# V2.net
KiCad netlist of a schematic drawn in Altium Designer
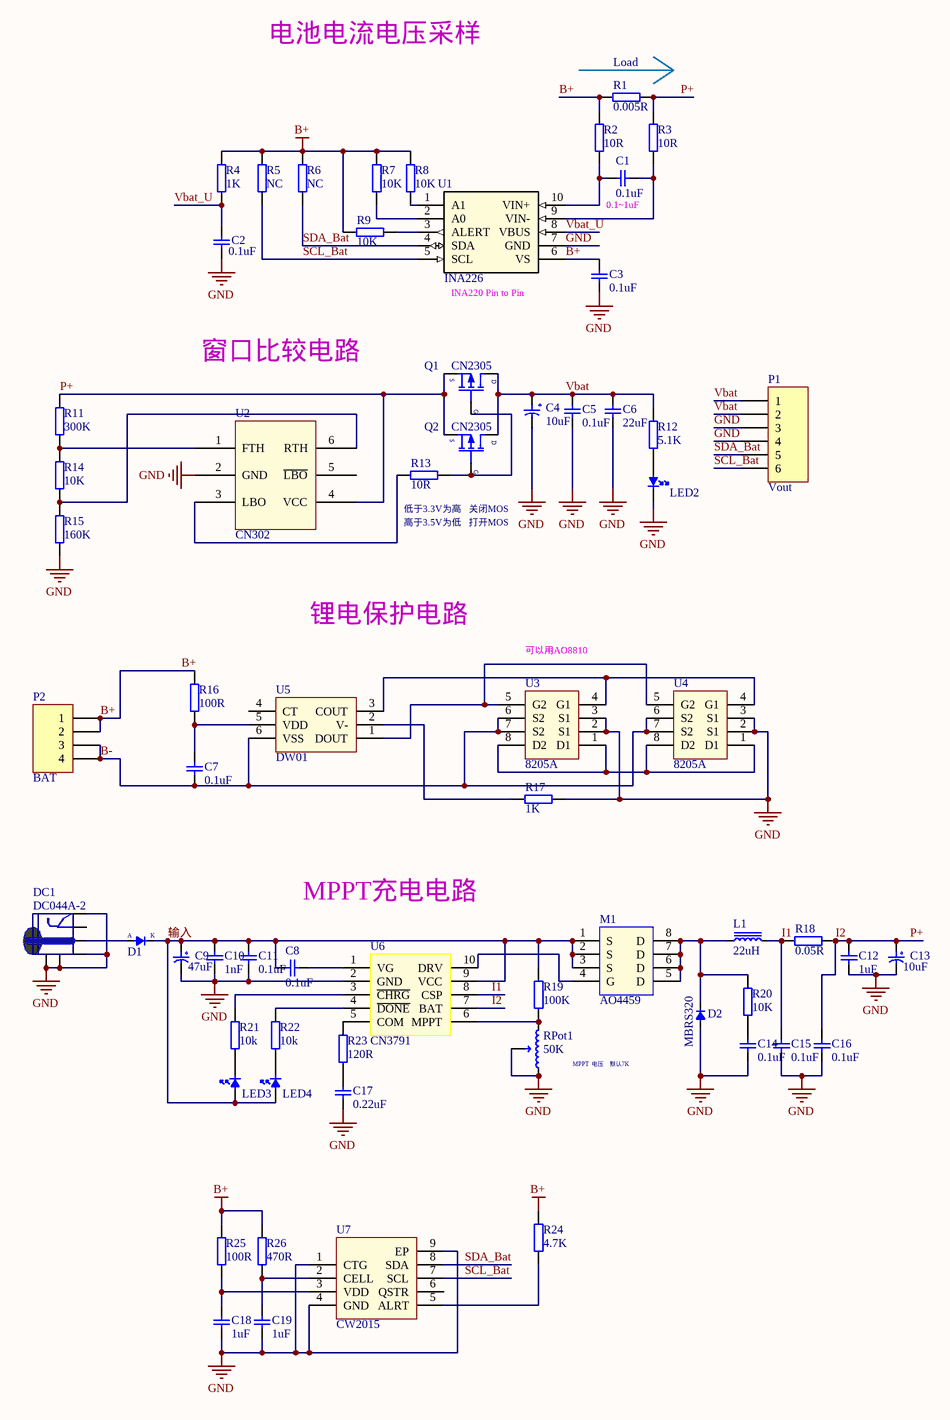
[diagram p0: 充放电模块V2.SchDoc]

(export (version "E")
  (design (tool "Eeschema 10.0.6"))
  (components
    (comp (ref "C1")
      (value "0.1uF")
      (footprint "0603-C")
      (description "Capacitor")
      (fields (field (name "PUBLISHER") "Altium Limited"))
      (libsource (lib "Schlib") (part "Cap"))
    )
    (comp (ref "C2")
      (value "0.1uF")
      (footprint "0603-C")
      (description "Capacitor")
      (fields (field (name "PUBLISHER") "Altium Limited"))
      (libsource (lib "Schlib") (part "Cap"))
    )
    (comp (ref "C3")
      (value "0.1uF")
      (footprint "0603-C")
      (description "Capacitor")
      (fields (field (name "PUBLISHER") "Altium Limited"))
      (libsource (lib "Schlib") (part "Cap"))
    )
    (comp (ref "C4") (value "10uF") (footprint "C6.3X6.3") (libsource (lib "") (part "Cap 有极性_1")))
    (comp (ref "C5")
      (value "0.1uF")
      (footprint "0603-C")
      (description "Capacitor")
      (fields (field (name "PUBLISHER") "Altium Limited"))
      (libsource (lib "Schlib") (part "Cap"))
    )
    (comp (ref "C6")
      (value "22uF")
      (footprint "1206 C")
      (description "Capacitor")
      (fields (field (name "PUBLISHER") "Altium Limited"))
      (libsource (lib "Schlib") (part "Cap"))
    )
    (comp (ref "C7")
      (value "0.1uF")
      (footprint "0603-C")
      (description "Capacitor")
      (fields (field (name "PUBLISHER") "Altium Limited"))
      (libsource (lib "Schlib") (part "Cap"))
    )
    (comp (ref "C8")
      (value "0.1uF")
      (footprint "0603-C")
      (description "Capacitor")
      (fields (field (name "PUBLISHER") "Altium Limited"))
      (libsource (lib "Schlib") (part "Cap"))
    )
    (comp (ref "C9") (value "47uF") (footprint "C8X8") (libsource (lib "Schlib") (part "Cap 有极性")))
    (comp (ref "C10")
      (value "1nF")
      (footprint "0603-C")
      (description "Capacitor")
      (fields (field (name "PUBLISHER") "Altium Limited"))
      (libsource (lib "Schlib") (part "Cap"))
    )
    (comp (ref "C11")
      (value "0.1uF")
      (footprint "0603-C")
      (description "Capacitor")
      (fields (field (name "PUBLISHER") "Altium Limited"))
      (libsource (lib "Schlib") (part "Cap"))
    )
    (comp (ref "C12")
      (value "1uF")
      (footprint "0603-C")
      (description "Capacitor")
      (fields (field (name "PUBLISHER") "Altium Limited"))
      (libsource (lib "Schlib") (part "Cap"))
    )
    (comp (ref "C13") (value "10uF") (footprint "C6.3X6.3") (libsource (lib "Schlib") (part "Cap 有极性")))
    (comp (ref "C14")
      (value "0.1uF")
      (footprint "0603-C")
      (description "Capacitor")
      (fields (field (name "PUBLISHER") "Altium Limited"))
      (libsource (lib "Schlib") (part "Cap"))
    )
    (comp (ref "C15")
      (value "0.1uF")
      (footprint "0603-C")
      (description "Capacitor")
      (fields (field (name "PUBLISHER") "Altium Limited"))
      (libsource (lib "Schlib") (part "Cap"))
    )
    (comp (ref "C16")
      (value "0.1uF")
      (footprint "0603-C")
      (description "Capacitor")
      (fields (field (name "PUBLISHER") "Altium Limited"))
      (libsource (lib "Schlib") (part "Cap"))
    )
    (comp (ref "C17")
      (value "0.22uF")
      (footprint "0603-C")
      (description "Capacitor")
      (fields (field (name "PUBLISHER") "Altium Limited"))
      (libsource (lib "Schlib") (part "Cap"))
    )
    (comp (ref "C18")
      (value "1uF")
      (footprint "0603-C")
      (description "Capacitor")
      (fields (field (name "PUBLISHER") "Altium Limited"))
      (libsource (lib "Schlib") (part "Cap"))
    )
    (comp (ref "C19")
      (value "1uF")
      (footprint "0603-C")
      (description "Capacitor")
      (fields (field (name "PUBLISHER") "Altium Limited"))
      (libsource (lib "Schlib") (part "Cap"))
    )
    (comp (ref "D1") (value "二极管") (footprint "DO-214") (libsource (lib "Schlib") (part "D")))
    (comp (ref "D2") (value "MBRS320") (footprint "DO-214AB") (libsource (lib "Schlib") (part "1N4148")))
    (comp (ref "DC1")
      (value "DC044A-2")
      (footprint "DC044A 6PIN")
      (description "6PIN")
      (libsource (lib "Schlib") (part "DC044A-2"))
    )
    (comp (ref "L1")
      (value "22uH")
      (footprint "L7X7")
      (description "Inductor")
      (fields (field (name "PUBLISHER") "Altium Limited"))
      (libsource (lib "Schlib") (part "Inductor"))
    )
    (comp (ref "LED2") (value "LED") (footprint "LED0805G") (libsource (lib "Schlib") (part "LED")))
    (comp (ref "LED3") (value "LED") (footprint "LED0805R") (libsource (lib "Schlib") (part "LED")))
    (comp (ref "LED4") (value "LED") (footprint "LED0805G") (libsource (lib "Schlib") (part "LED")))
    (comp (ref "M1") (value "AO4459") (footprint "SOP8") (libsource (lib "Schlib") (part "AO4459")))
    (comp (ref "P1")
      (value "Vout")
      (footprint "XHS2.5-6P")
      (description "Header, 6-Pin")
      (fields (field (name "PUBLISHER") "Altium Limited"))
      (libsource (lib "Miscellaneous Connectors") (part "Header 6"))
    )
    (comp (ref "P2")
      (value "BAT")
      (footprint "XH 2.5 AW 4PIN")
      (description "Header, 4-Pin")
      (fields (field (name "PUBLISHER") "Altium Limited"))
      (libsource (lib "Miscellaneous Connectors") (part "Header 4"))
    )
    (comp (ref "Q1") (value "CN2305") (footprint "SOT23") (libsource (lib "Schlib") (part "CN2305")))
    (comp (ref "Q2") (value "CN2305") (footprint "SOT23") (libsource (lib "Schlib") (part "CN2305")))
    (comp (ref "R1")
      (value "0.005R")
      (footprint "1210R")
      (description "Resistor")
      (libsource (lib "") (part "Res2_3"))
    )
    (comp (ref "R2")
      (value "10R")
      (footprint "0603-r")
      (description "Resistor")
      (libsource (lib "Schlib") (part "Res2"))
    )
    (comp (ref "R3")
      (value "10R")
      (footprint "0603-r")
      (description "Resistor")
      (libsource (lib "Schlib") (part "Res2"))
    )
    (comp (ref "R4")
      (value "1K")
      (footprint "0603-r")
      (description "Resistor")
      (libsource (lib "") (part "Res2_1"))
    )
    (comp (ref "R5")
      (value "NC")
      (footprint "0603-r")
      (description "Resistor")
      (libsource (lib "Schlib") (part "Res2"))
    )
    (comp (ref "R6")
      (value "NC")
      (footprint "0603-r")
      (description "Resistor")
      (libsource (lib "Schlib") (part "Res2"))
    )
    (comp (ref "R7")
      (value "10K")
      (footprint "0603-r")
      (description "Resistor")
      (libsource (lib "Schlib") (part "Res2"))
    )
    (comp (ref "R8")
      (value "10K")
      (footprint "0603-r")
      (description "Resistor")
      (libsource (lib "Schlib") (part "Res2"))
    )
    (comp (ref "R9")
      (value "10K")
      (footprint "0603-r")
      (description "Resistor")
      (libsource (lib "") (part "Res2_1"))
    )
    (comp (ref "R11")
      (value "300K")
      (footprint "0603-r")
      (description "Resistor")
      (libsource (lib "") (part "Res2_3"))
    )
    (comp (ref "R12")
      (value "5.1K")
      (footprint "0603-r")
      (description "Resistor")
      (libsource (lib "") (part "Res2_2"))
    )
    (comp (ref "R13")
      (value "10R")
      (footprint "0603-r")
      (description "Resistor")
      (libsource (lib "") (part "Res2_2"))
    )
    (comp (ref "R14")
      (value "10K")
      (footprint "0603-r")
      (description "Resistor")
      (libsource (lib "") (part "Res2_3"))
    )
    (comp (ref "R15")
      (value "160K")
      (footprint "0603-r")
      (description "Resistor")
      (libsource (lib "") (part "Res2_3"))
    )
    (comp (ref "R16")
      (value "100R")
      (footprint "0603-r")
      (description "Resistor")
      (libsource (lib "") (part "Res2_1"))
    )
    (comp (ref "R17")
      (value "1K")
      (footprint "0603-r")
      (description "Resistor")
      (libsource (lib "") (part "Res2_3"))
    )
    (comp (ref "R18")
      (value "0.05R")
      (footprint "1210R")
      (description "Resistor")
      (libsource (lib "") (part "Res2_3"))
    )
    (comp (ref "R19")
      (value "100K")
      (footprint "0603-r")
      (description "Resistor")
      (libsource (lib "") (part "Res2_2"))
    )
    (comp (ref "R20")
      (value "10K")
      (footprint "0603-r")
      (description "Resistor")
      (libsource (lib "") (part "Res2_2"))
    )
    (comp (ref "R21")
      (value "10k")
      (footprint "0603-r")
      (description "Resistor")
      (libsource (lib "") (part "Res2_2"))
    )
    (comp (ref "R22")
      (value "10k")
      (footprint "0603-r")
      (description "Resistor")
      (libsource (lib "") (part "Res2_2"))
    )
    (comp (ref "R23")
      (value "120R")
      (footprint "0603-r")
      (description "Resistor")
      (libsource (lib "") (part "Res2_2"))
    )
    (comp (ref "R24")
      (value "4.7K")
      (footprint "0603-r")
      (description "Resistor")
      (libsource (lib "") (part "Res2_2"))
    )
    (comp (ref "R25")
      (value "100R")
      (footprint "0603-r")
      (description "Resistor")
      (libsource (lib "") (part "Res2_2"))
    )
    (comp (ref "R26")
      (value "470R")
      (footprint "0603-r")
      (description "Resistor")
      (libsource (lib "") (part "Res2_2"))
    )
    (comp (ref "RPot1") (value "50K") (footprint "VR5 - W") (libsource (lib "Schlib") (part "可调电阻")))
    (comp (ref "U1")
      (value "INA226")
      (footprint "DGS10")
      (description "Imported")
      (fields
        (field (name "MANUFACTURER") "Texas Instruments")
        (field (name "MANUFACTURER_PART_NUMBER") "ina226_dgs_10")
      )
      (libsource (lib "Schlib") (part "INA226_DGS_10"))
    )
    (comp (ref "U2")
      (value "CN302")
      (footprint "其他:SOT23-6")
      (description "如韵电池检测")
      (libsource (lib "Schlib") (part "CN302"))
    )
    (comp (ref "U3") (value "8205A") (footprint "TSSOP8-MCP730P") (libsource (lib "Schlib") (part "8205A")))
    (comp (ref "U4") (value "8205A") (footprint "TSSOP8-MCP730P") (libsource (lib "Schlib") (part "8205A")))
    (comp (ref "U5") (value "DW01") (footprint "SOT23-6") (libsource (lib "Schlib") (part "DW01")))
    (comp (ref "U6") (value "CN3791") (footprint "SSOP10") (libsource (lib "Schlib") (part "CN3791")))
    (comp (ref "U7") (value "CW2015") (footprint "QFN-8") (libsource (lib "Schlib") (part "CW2015")))
  )
  (nets
    (net (code "1") (name "/B-") (class "Default")
      (node (ref "C7") (pin "2") (pinfunction "2_2") (pintype "passive"))
      (node (ref "P2") (pin "3") (pinfunction "3_3") (pintype "passive"))
      (node (ref "P2") (pin "4") (pinfunction "4_4") (pintype "passive"))
      (node (ref "U3") (pin "6") (pinfunction "S2_6") (pintype "passive"))
      (node (ref "U3") (pin "7") (pinfunction "S2_7") (pintype "passive"))
      (node (ref "U4") (pin "6") (pinfunction "S2_6") (pintype "passive"))
      (node (ref "U4") (pin "7") (pinfunction "S2_7") (pintype "passive"))
      (node (ref "U5") (pin "6") (pinfunction "VSS_6") (pintype "passive"))
    )
    (net (code "2") (name "/I1") (class "Default")
      (node (ref "C15") (pin "1") (pinfunction "1_1") (pintype "passive"))
      (node (ref "L1") (pin "2") (pinfunction "2_2") (pintype "passive"))
      (node (ref "R18") (pin "2") (pinfunction "2_2") (pintype "passive"))
      (node (ref "U6") (pin "8") (pinfunction "CSP_8") (pintype "passive"))
    )
    (net (code "3") (name "/I2") (class "Default")
      (node (ref "C12") (pin "1") (pinfunction "1_1") (pintype "passive"))
      (node (ref "C13") (pin "1") (pinfunction "1_1") (pintype "passive"))
      (node (ref "C16") (pin "1") (pinfunction "1_1") (pintype "passive"))
      (node (ref "Q1") (pin "3") (pinfunction "S_3") (pintype "passive"))
      (node (ref "Q2") (pin "3") (pinfunction "S_3") (pintype "passive"))
      (node (ref "R1") (pin "1") (pinfunction "1_1") (pintype "passive"))
      (node (ref "R11") (pin "1") (pinfunction "1_1") (pintype "passive"))
      (node (ref "R18") (pin "1") (pinfunction "1_1") (pintype "passive"))
      (node (ref "R3") (pin "2") (pinfunction "2_2") (pintype "passive"))
      (node (ref "U2") (pin "4") (pinfunction "VCC_4") (pintype "passive"))
      (node (ref "U6") (pin "7") (pinfunction "BAT_7") (pintype "passive"))
    )
    (net (code "4") (name "/SCL_Bat") (class "Default")
      (node (ref "P1") (pin "6") (pinfunction "6_6") (pintype "passive"))
      (node (ref "R5") (pin "1") (pinfunction "1_1") (pintype "passive"))
      (node (ref "U1") (pin "5") (pinfunction "SCL_5") (pintype "input"))
      (node (ref "U7") (pin "7") (pinfunction "SCL_7") (pintype "passive"))
    )
    (net (code "5") (name "/SDA_Bat") (class "Default")
      (node (ref "P1") (pin "5") (pinfunction "5_5") (pintype "passive"))
      (node (ref "R6") (pin "1") (pinfunction "1_1") (pintype "passive"))
      (node (ref "U1") (pin "4") (pinfunction "SDA_4") (pintype "bidirectional"))
      (node (ref "U7") (pin "8") (pinfunction "SDA_8") (pintype "passive"))
    )
    (net (code "6") (name "/Vbat") (class "Default")
      (node (ref "C4") (pin "1") (pinfunction "1_1") (pintype "passive"))
      (node (ref "C5") (pin "1") (pinfunction "1_1") (pintype "passive"))
      (node (ref "C6") (pin "1") (pinfunction "1_1") (pintype "passive"))
      (node (ref "P1") (pin "1") (pinfunction "1_1") (pintype "passive"))
      (node (ref "P1") (pin "2") (pinfunction "2_2") (pintype "passive"))
      (node (ref "Q1") (pin "2") (pinfunction "D_2") (pintype "passive"))
      (node (ref "Q2") (pin "2") (pinfunction "D_2") (pintype "passive"))
      (node (ref "R12") (pin "2") (pinfunction "2_2") (pintype "passive"))
    )
    (net (code "7") (name "/Vbat_U") (class "Default")
      (node (ref "C2") (pin "2") (pinfunction "2_2") (pintype "passive"))
      (node (ref "R4") (pin "2") (pinfunction "2_2") (pintype "passive"))
      (node (ref "U1") (pin "8") (pinfunction "VBUS_8") (pintype "input"))
    )
    (net (code "8") (name "/输入") (class "Default")
      (node (ref "C10") (pin "1") (pinfunction "1_1") (pintype "passive"))
      (node (ref "C11") (pin "1") (pinfunction "1_1") (pintype "passive"))
      (node (ref "C8") (pin "2") (pinfunction "2_2") (pintype "passive"))
      (node (ref "C9") (pin "1") (pinfunction "1_1") (pintype "passive"))
      (node (ref "D1") (pin "2") (pinfunction "K_2") (pintype "passive"))
      (node (ref "LED3") (pin "1") (pinfunction "1_1") (pintype "passive"))
      (node (ref "LED4") (pin "1") (pinfunction "1_1") (pintype "passive"))
      (node (ref "M1") (pin "1") (pinfunction "S_1") (pintype "passive"))
      (node (ref "M1") (pin "2") (pinfunction "S_2") (pintype "passive"))
      (node (ref "M1") (pin "3") (pinfunction "S_3") (pintype "passive"))
      (node (ref "R19") (pin "2") (pinfunction "2_2") (pintype "passive"))
      (node (ref "U6") (pin "9") (pinfunction "VCC_9") (pintype "passive"))
    )
    (net (code "9") (name "B+") (class "Default")
      (node (ref "C3") (pin "1") (pinfunction "1_1") (pintype "passive"))
      (node (ref "P2") (pin "1") (pinfunction "1_1") (pintype "passive"))
      (node (ref "P2") (pin "2") (pinfunction "2_2") (pintype "passive"))
      (node (ref "R1") (pin "2") (pinfunction "2_2") (pintype "passive"))
      (node (ref "R16") (pin "1") (pinfunction "1_1") (pintype "passive"))
      (node (ref "R2") (pin "2") (pinfunction "2_2") (pintype "passive"))
      (node (ref "R24") (pin "2") (pinfunction "2_2") (pintype "passive"))
      (node (ref "R25") (pin "2") (pinfunction "2_2") (pintype "passive"))
      (node (ref "R26") (pin "2") (pinfunction "2_2") (pintype "passive"))
      (node (ref "R4") (pin "1") (pinfunction "1_1") (pintype "passive"))
      (node (ref "R5") (pin "2") (pinfunction "2_2") (pintype "passive"))
      (node (ref "R6") (pin "2") (pinfunction "2_2") (pintype "passive"))
      (node (ref "R7") (pin "2") (pinfunction "2_2") (pintype "passive"))
      (node (ref "R8") (pin "2") (pinfunction "2_2") (pintype "passive"))
      (node (ref "R9") (pin "2") (pinfunction "2_2") (pintype "passive"))
      (node (ref "U1") (pin "6") (pinfunction "VS_6") (pintype "power_in"))
    )
    (net (code "10") (name "GND") (class "Default")
      (node (ref "C10") (pin "2") (pinfunction "2_2") (pintype "passive"))
      (node (ref "C11") (pin "2") (pinfunction "2_2") (pintype "passive"))
      (node (ref "C12") (pin "2") (pinfunction "2_2") (pintype "passive"))
      (node (ref "C13") (pin "2") (pinfunction "2_2") (pintype "passive"))
      (node (ref "C14") (pin "2") (pinfunction "2_2") (pintype "passive"))
      (node (ref "C15") (pin "2") (pinfunction "2_2") (pintype "passive"))
      (node (ref "C16") (pin "2") (pinfunction "2_2") (pintype "passive"))
      (node (ref "C17") (pin "2") (pinfunction "2_2") (pintype "passive"))
      (node (ref "C18") (pin "1") (pinfunction "1_1") (pintype "passive"))
      (node (ref "C19") (pin "1") (pinfunction "1_1") (pintype "passive"))
      (node (ref "C2") (pin "1") (pinfunction "1_1") (pintype "passive"))
      (node (ref "C3") (pin "2") (pinfunction "2_2") (pintype "passive"))
      (node (ref "C4") (pin "2") (pinfunction "2_2") (pintype "passive"))
      (node (ref "C5") (pin "2") (pinfunction "2_2") (pintype "passive"))
      (node (ref "C6") (pin "2") (pinfunction "2_2") (pintype "passive"))
      (node (ref "C9") (pin "2") (pinfunction "2_2") (pintype "passive"))
      (node (ref "D2") (pin "1") (pinfunction "1_1") (pintype "passive"))
      (node (ref "DC1") (pin "1") (pinfunction "1_1") (pintype "passive"))
      (node (ref "DC1") (pin "2") (pinfunction "2_2") (pintype "passive"))
      (node (ref "DC1") (pin "4") (pinfunction "4_4") (pintype "passive"))
      (node (ref "DC1") (pin "5") (pinfunction "5_5") (pintype "passive"))
      (node (ref "LED2") (pin "2") (pinfunction "2_2") (pintype "passive"))
      (node (ref "P1") (pin "3") (pinfunction "3_3") (pintype "passive"))
      (node (ref "P1") (pin "4") (pinfunction "4_4") (pintype "passive"))
      (node (ref "R15") (pin "2") (pinfunction "2_2") (pintype "passive"))
      (node (ref "R17") (pin "1") (pinfunction "1_1") (pintype "passive"))
      (node (ref "RPot1") (pin "1") (pinfunction "1_1") (pintype "passive"))
      (node (ref "RPot1") (pin "2") (pinfunction "2_2") (pintype "passive"))
      (node (ref "U1") (pin "7") (pinfunction "GND_7") (pintype "power_in"))
      (node (ref "U2") (pin "2") (pinfunction "GND_2") (pintype "passive"))
      (node (ref "U3") (pin "2") (pinfunction "S1_2") (pintype "passive"))
      (node (ref "U3") (pin "3") (pinfunction "S1_3") (pintype "passive"))
      (node (ref "U4") (pin "2") (pinfunction "S1_2") (pintype "passive"))
      (node (ref "U4") (pin "3") (pinfunction "S1_3") (pintype "passive"))
      (node (ref "U6") (pin "2") (pinfunction "GND_2") (pintype "passive"))
      (node (ref "U7") (pin "1") (pinfunction "CTG_1") (pintype "passive"))
      (node (ref "U7") (pin "4") (pinfunction "GND_4") (pintype "passive"))
      (node (ref "U7") (pin "9") (pinfunction "EP_9") (pintype "passive"))
    )
    (net (code "11") (name "Net-(C14-Pad1)") (class "Default")
      (node (ref "C14") (pin "1") (pinfunction "1_1") (pintype "passive"))
      (node (ref "R20") (pin "1") (pinfunction "1_1") (pintype "passive"))
    )
    (net (code "12") (name "Net-(C17-Pad1)") (class "Default")
      (node (ref "C17") (pin "1") (pinfunction "1_1") (pintype "passive"))
      (node (ref "R23") (pin "1") (pinfunction "1_1") (pintype "passive"))
    )
    (net (code "13") (name "Net-(D1-A)") (class "Default")
      (node (ref "D1") (pin "1") (pinfunction "A_1") (pintype "passive"))
      (node (ref "DC1") (pin "3") (pinfunction "3_3") (pintype "passive"))
    )
    (net (code "14") (name "Net-(D2-Pad2)") (class "Default")
      (node (ref "D2") (pin "2") (pinfunction "2_2") (pintype "passive"))
      (node (ref "L1") (pin "1") (pinfunction "1_1") (pintype "passive"))
      (node (ref "M1") (pin "5") (pinfunction "D_5") (pintype "passive"))
      (node (ref "M1") (pin "6") (pinfunction "D_6") (pintype "passive"))
      (node (ref "M1") (pin "7") (pinfunction "D_7") (pintype "passive"))
      (node (ref "M1") (pin "8") (pinfunction "D_8") (pintype "passive"))
      (node (ref "R20") (pin "2") (pinfunction "2_2") (pintype "passive"))
    )
    (net (code "15") (name "Net-(LED2-Pad1)") (class "Default")
      (node (ref "LED2") (pin "1") (pinfunction "1_1") (pintype "passive"))
      (node (ref "R12") (pin "1") (pinfunction "1_1") (pintype "passive"))
    )
    (net (code "16") (name "Net-(LED3-Pad2)") (class "Default")
      (node (ref "LED3") (pin "2") (pinfunction "2_2") (pintype "passive"))
      (node (ref "R21") (pin "1") (pinfunction "1_1") (pintype "passive"))
    )
    (net (code "17") (name "Net-(LED4-Pad2)") (class "Default")
      (node (ref "LED4") (pin "2") (pinfunction "2_2") (pintype "passive"))
      (node (ref "R22") (pin "1") (pinfunction "1_1") (pintype "passive"))
    )
    (net (code "18") (name "Net-(M1-G)") (class "Default")
      (node (ref "M1") (pin "4") (pinfunction "G_4") (pintype "passive"))
      (node (ref "U6") (pin "10") (pinfunction "DRV_10") (pintype "passive"))
    )
    (net (code "19") (name "Net-(Q1-G)") (class "Default")
      (node (ref "Q1") (pin "1") (pinfunction "G_1") (pintype "passive"))
      (node (ref "Q2") (pin "1") (pinfunction "G_1") (pintype "passive"))
      (node (ref "R13") (pin "2") (pinfunction "2_2") (pintype "passive"))
    )
    (net (code "20") (name "Net-(U1-A0)") (class "Default")
      (node (ref "R7") (pin "1") (pinfunction "1_1") (pintype "passive"))
      (node (ref "U1") (pin "2") (pinfunction "A0_2") (pintype "passive"))
    )
    (net (code "21") (name "Net-(U1-A1)") (class "Default")
      (node (ref "R8") (pin "1") (pinfunction "1_1") (pintype "passive"))
      (node (ref "U1") (pin "1") (pinfunction "A1_1") (pintype "passive"))
    )
    (net (code "22") (name "Net-(U1-ALERT)") (class "Default")
      (node (ref "R9") (pin "1") (pinfunction "1_1") (pintype "passive"))
      (node (ref "U1") (pin "3") (pinfunction "ALERT_3") (pintype "output"))
    )
    (net (code "23") (name "Net-(U1-VIN+)") (class "Default")
      (node (ref "C1") (pin "2") (pinfunction "2_2") (pintype "passive"))
      (node (ref "R2") (pin "1") (pinfunction "1_1") (pintype "passive"))
      (node (ref "U1") (pin "10") (pinfunction "VIN+_10") (pintype "input"))
    )
    (net (code "24") (name "Net-(U1-VIN-)") (class "Default")
      (node (ref "C1") (pin "1") (pinfunction "1_1") (pintype "passive"))
      (node (ref "R3") (pin "1") (pinfunction "1_1") (pintype "passive"))
      (node (ref "U1") (pin "9") (pinfunction "VIN-_9") (pintype "input"))
    )
    (net (code "25") (name "Net-(U2-FTH)") (class "Default")
      (node (ref "R11") (pin "2") (pinfunction "2_2") (pintype "passive"))
      (node (ref "R14") (pin "1") (pinfunction "1_1") (pintype "passive"))
      (node (ref "U2") (pin "1") (pinfunction "FTH_1") (pintype "passive"))
    )
    (net (code "26") (name "Net-(U2-LBO)") (class "Default")
      (node (ref "R13") (pin "1") (pinfunction "1_1") (pintype "passive"))
      (node (ref "U2") (pin "3") (pinfunction "LBO_3") (pintype "passive"))
    )
    (net (code "27") (name "Net-(U2-RTH)") (class "Default")
      (node (ref "R14") (pin "2") (pinfunction "2_2") (pintype "passive"))
      (node (ref "R15") (pin "1") (pinfunction "1_1") (pintype "passive"))
      (node (ref "U2") (pin "6") (pinfunction "RTH_6") (pintype "passive"))
    )
    (net (code "28") (name "Net-(U3-D1)") (class "Default")
      (node (ref "U3") (pin "1") (pinfunction "D1_1") (pintype "passive"))
      (node (ref "U3") (pin "8") (pinfunction "D2_8") (pintype "passive"))
      (node (ref "U4") (pin "1") (pinfunction "D1_1") (pintype "passive"))
      (node (ref "U4") (pin "8") (pinfunction "D2_8") (pintype "passive"))
    )
    (net (code "29") (name "Net-(U3-G1)") (class "Default")
      (node (ref "U3") (pin "4") (pinfunction "G1_4") (pintype "passive"))
      (node (ref "U4") (pin "4") (pinfunction "G1_4") (pintype "passive"))
      (node (ref "U5") (pin "3") (pinfunction "COUT_3") (pintype "passive"))
    )
    (net (code "30") (name "Net-(U3-G2)") (class "Default")
      (node (ref "U3") (pin "5") (pinfunction "G2_5") (pintype "passive"))
      (node (ref "U4") (pin "5") (pinfunction "G2_5") (pintype "passive"))
      (node (ref "U5") (pin "1") (pinfunction "DOUT_1") (pintype "passive"))
    )
    (net (code "31") (name "Net-(U5-V-)") (class "Default")
      (node (ref "R17") (pin "2") (pinfunction "2_2") (pintype "passive"))
      (node (ref "U5") (pin "2") (pinfunction "V-_2") (pintype "passive"))
    )
    (net (code "32") (name "Net-(U5-VDD)") (class "Default")
      (node (ref "C7") (pin "1") (pinfunction "1_1") (pintype "passive"))
      (node (ref "R16") (pin "2") (pinfunction "2_2") (pintype "passive"))
      (node (ref "U5") (pin "5") (pinfunction "VDD_5") (pintype "passive"))
    )
    (net (code "33") (name "Net-(U6-COM)") (class "Default")
      (node (ref "R23") (pin "2") (pinfunction "2_2") (pintype "passive"))
      (node (ref "U6") (pin "5") (pinfunction "COM_5") (pintype "passive"))
    )
    (net (code "34") (name "Net-(U6-MPPT)") (class "Default")
      (node (ref "R19") (pin "1") (pinfunction "1_1") (pintype "passive"))
      (node (ref "RPot1") (pin "3") (pinfunction "3_3") (pintype "passive"))
      (node (ref "U6") (pin "6") (pinfunction "MPPT_6") (pintype "passive"))
    )
    (net (code "35") (name "Net-(U6-VG)") (class "Default")
      (node (ref "C8") (pin "1") (pinfunction "1_1") (pintype "passive"))
      (node (ref "U6") (pin "1") (pinfunction "VG_1") (pintype "passive"))
    )
    (net (code "36") (name "Net-(U6-~{CHRG})") (class "Default")
      (node (ref "R21") (pin "2") (pinfunction "2_2") (pintype "passive"))
      (node (ref "U6") (pin "3") (pinfunction "~{CHRG}_3") (pintype "passive"))
    )
    (net (code "37") (name "Net-(U6-~{DONE})") (class "Default")
      (node (ref "R22") (pin "2") (pinfunction "2_2") (pintype "passive"))
      (node (ref "U6") (pin "4") (pinfunction "~{DONE}_4") (pintype "passive"))
    )
    (net (code "38") (name "Net-(U7-ALRT)") (class "Default")
      (node (ref "R24") (pin "1") (pinfunction "1_1") (pintype "passive"))
      (node (ref "U7") (pin "5") (pinfunction "ALRT_5") (pintype "passive"))
    )
    (net (code "39") (name "Net-(U7-CELL)") (class "Default")
      (node (ref "C19") (pin "2") (pinfunction "2_2") (pintype "passive"))
      (node (ref "R26") (pin "1") (pinfunction "1_1") (pintype "passive"))
      (node (ref "U7") (pin "2") (pinfunction "CELL_2") (pintype "passive"))
    )
    (net (code "40") (name "Net-(U7-VDD)") (class "Default")
      (node (ref "C18") (pin "2") (pinfunction "2_2") (pintype "passive"))
      (node (ref "R25") (pin "1") (pinfunction "1_1") (pintype "passive"))
      (node (ref "U7") (pin "3") (pinfunction "VDD_3") (pintype "passive"))
    )
    (net (code "41") (name "unconnected-(DC1-Pad6)") (class "Default")
      (node (ref "DC1") (pin "6") (pinfunction "6_6") (pintype "passive"))
    )
    (net (code "42") (name "unconnected-(U2-~{LBO}-Pad5)") (class "Default")
      (node (ref "U2") (pin "5") (pinfunction "~{LBO}_5") (pintype "passive"))
    )
    (net (code "43") (name "unconnected-(U5-CT-Pad4)") (class "Default")
      (node (ref "U5") (pin "4") (pinfunction "CT_4") (pintype "passive"))
    )
    (net (code "44") (name "unconnected-(U7-QSTR-Pad6)") (class "Default")
      (node (ref "U7") (pin "6") (pinfunction "QSTR_6") (pintype "passive"))
    )
  )
)
